# Secondary_Board_1_0.net
KiCad netlist of a schematic drawn in EAGLE
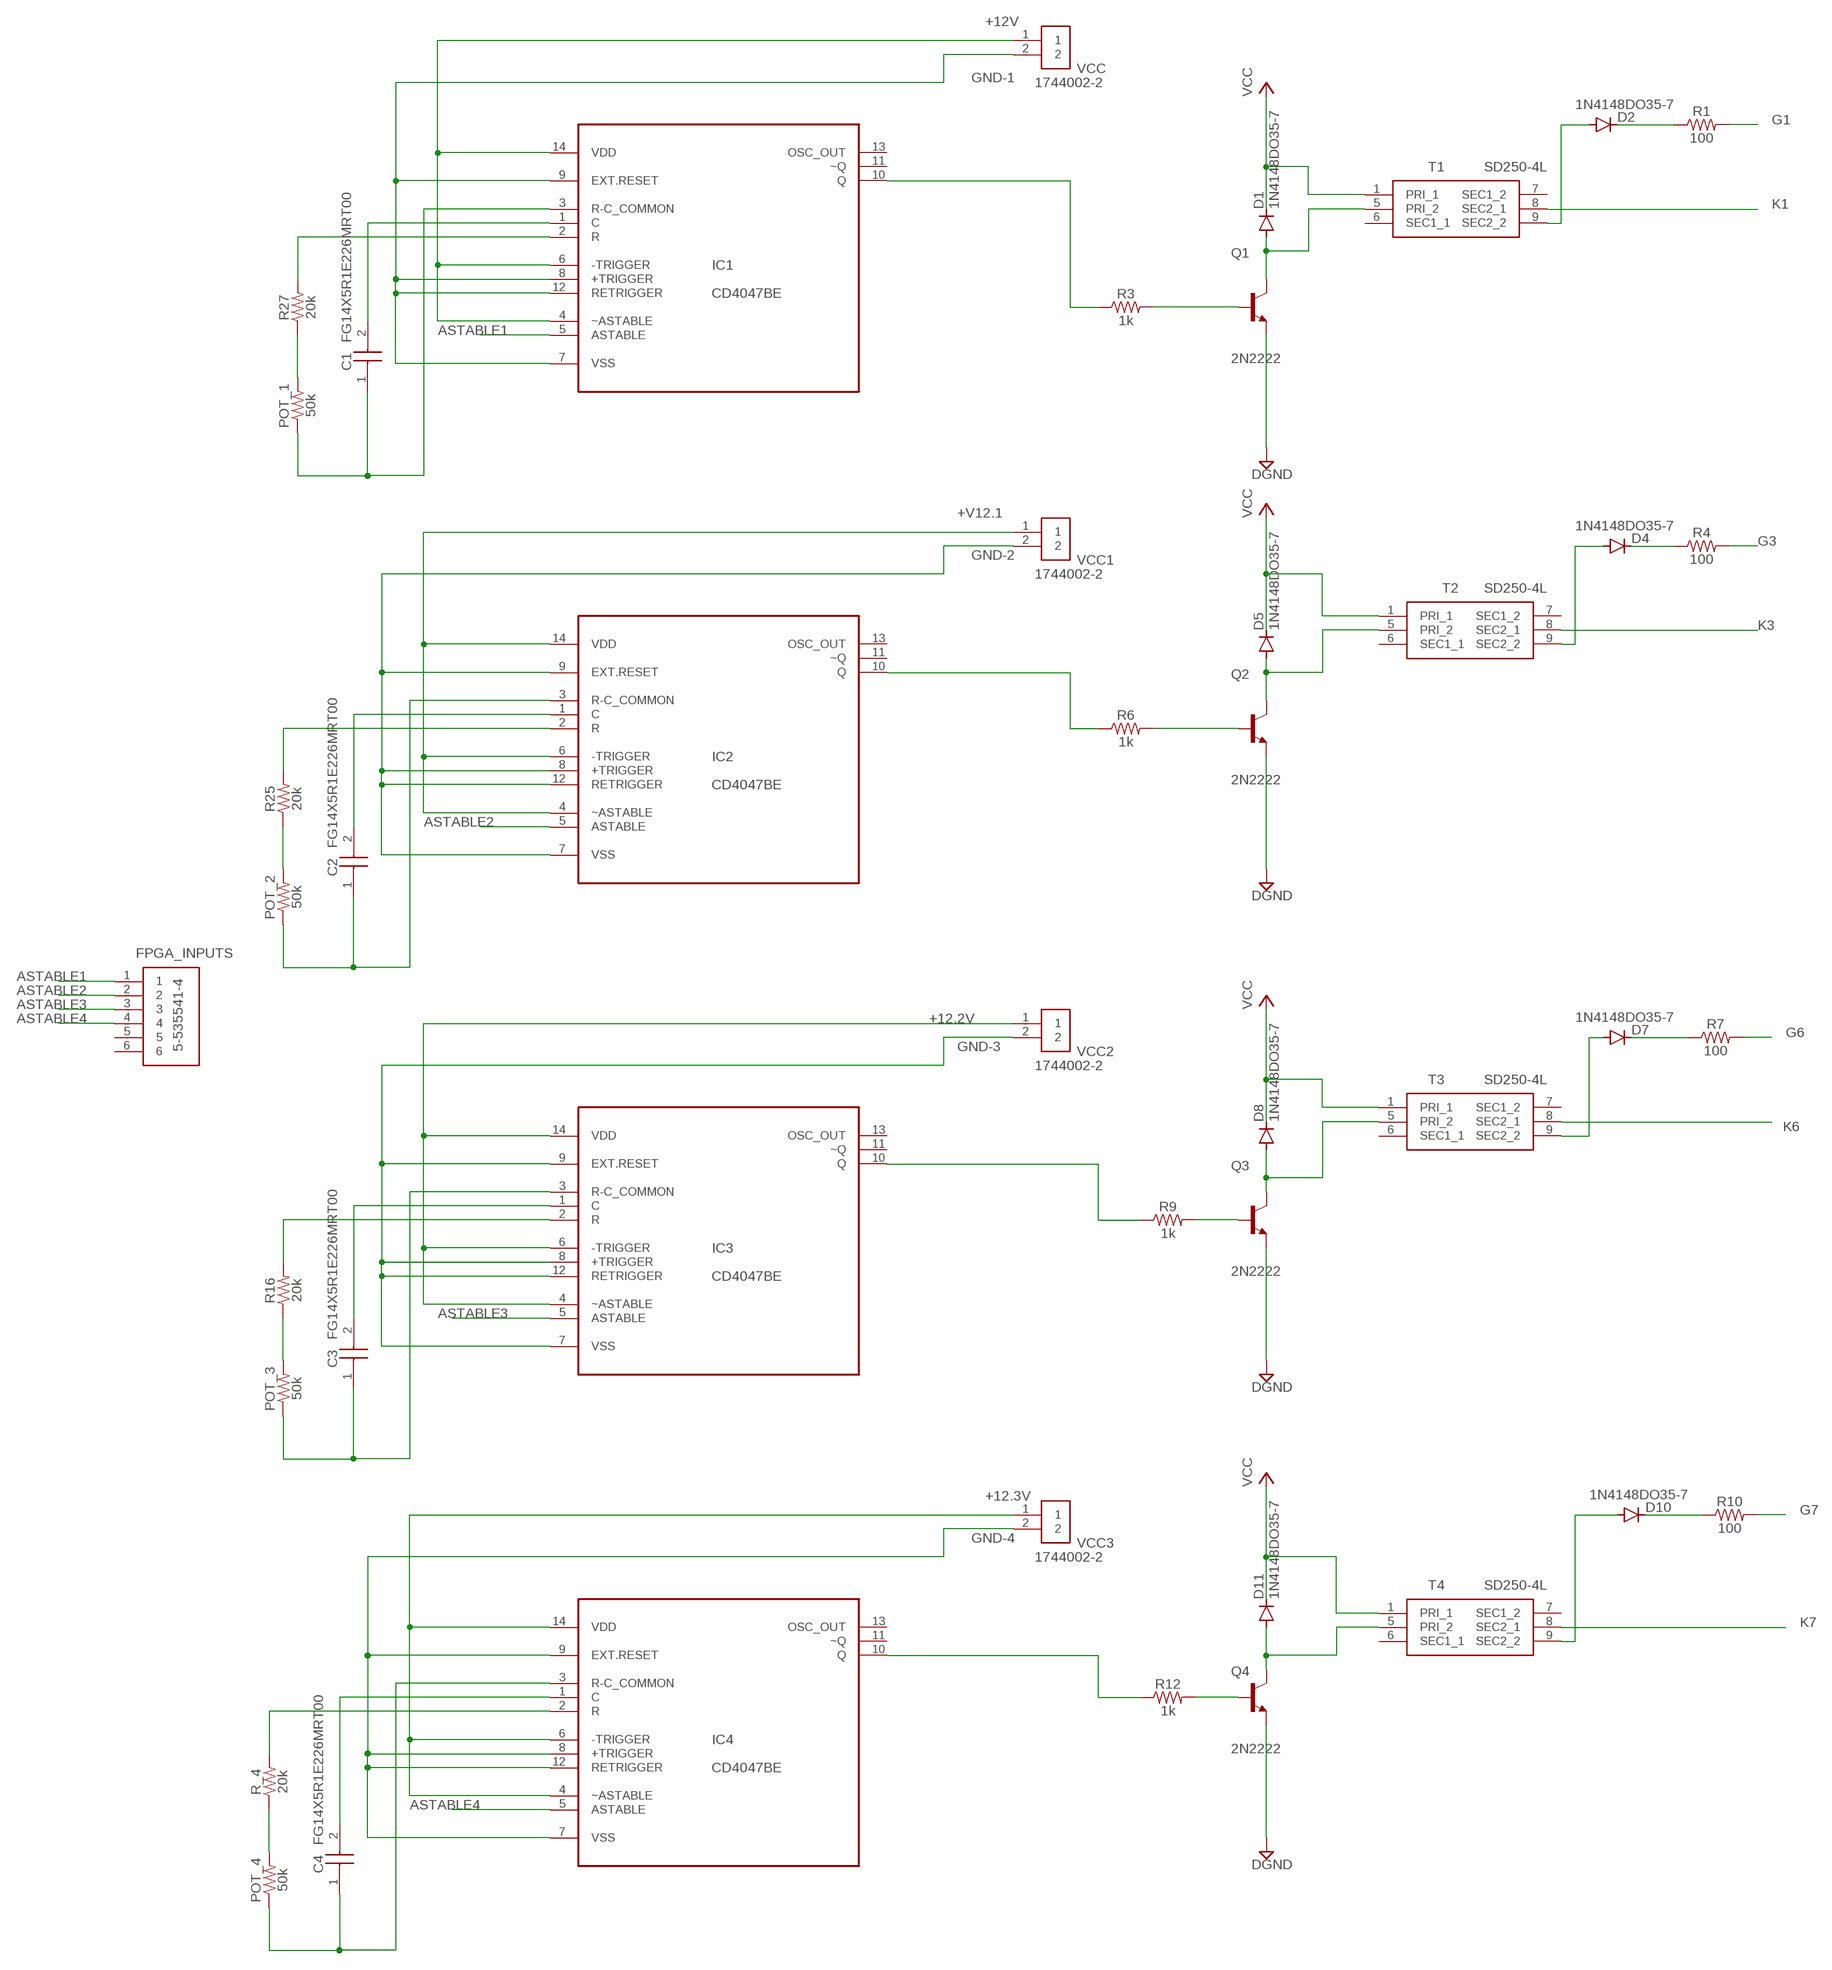
[diagram p0: schematic, sheet 1, part 1 of 2]
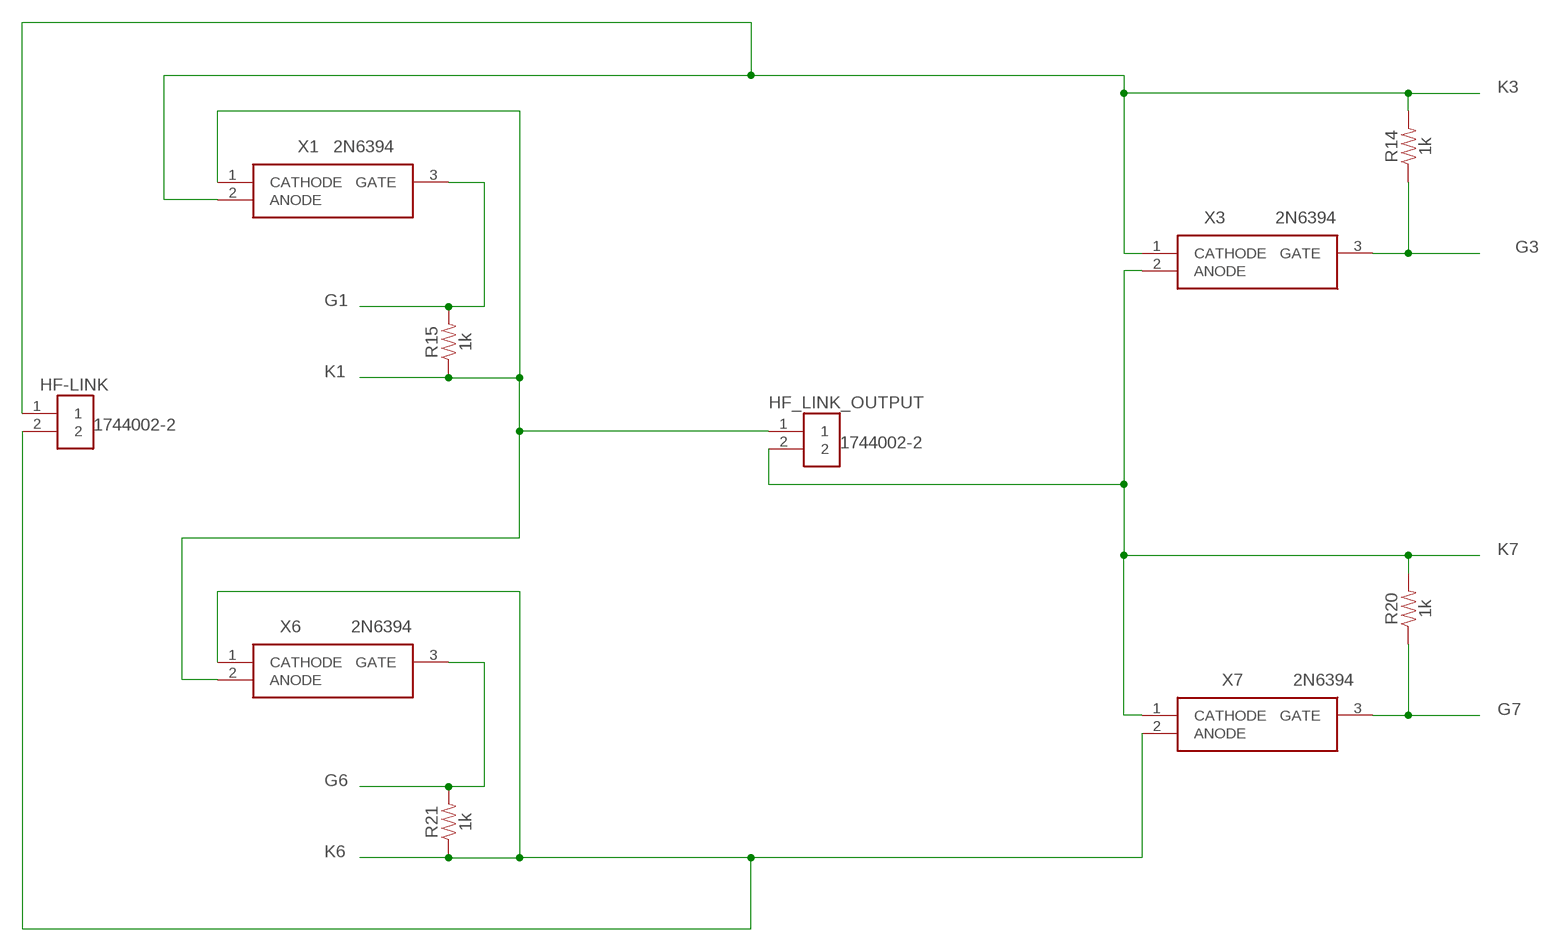
[diagram p1: schematic, sheet 1, part 2 of 2]

(export (version "E")
  (design (tool "Eeschema 10.0.6"))
  (components
    (comp (ref "C1")
      (value "FG14X5R1E226MRT00")
      (footprint "eagle-import:CAPPRD550W50D395H550")
      (libsource (lib "eagle-import") (part "FG14X5R1E226MRT00"))
    )
    (comp (ref "C2")
      (value "FG14X5R1E226MRT00")
      (footprint "eagle-import:CAPPRD550W50D395H550")
      (libsource (lib "eagle-import") (part "FG14X5R1E226MRT00"))
    )
    (comp (ref "C3")
      (value "FG14X5R1E226MRT00")
      (footprint "eagle-import:CAPPRD550W50D395H550")
      (libsource (lib "eagle-import") (part "FG14X5R1E226MRT00"))
    )
    (comp (ref "C4")
      (value "FG14X5R1E226MRT00")
      (footprint "eagle-import:CAPPRD550W50D395H550")
      (libsource (lib "eagle-import") (part "FG14X5R1E226MRT00"))
    )
    (comp (ref "D1")
      (value "1N4148DO35-7")
      (footprint "eagle-import:DO35-7")
      (libsource (lib "eagle-import") (part "1N4148DO35-7"))
    )
    (comp (ref "D2")
      (value "1N4148DO35-7")
      (footprint "eagle-import:DO35-7")
      (libsource (lib "eagle-import") (part "1N4148DO35-7"))
    )
    (comp (ref "D4")
      (value "1N4148DO35-7")
      (footprint "eagle-import:DO35-7")
      (libsource (lib "eagle-import") (part "1N4148DO35-7"))
    )
    (comp (ref "D5")
      (value "1N4148DO35-7")
      (footprint "eagle-import:DO35-7")
      (libsource (lib "eagle-import") (part "1N4148DO35-7"))
    )
    (comp (ref "D7")
      (value "1N4148DO35-7")
      (footprint "eagle-import:DO35-7")
      (libsource (lib "eagle-import") (part "1N4148DO35-7"))
    )
    (comp (ref "D8")
      (value "1N4148DO35-7")
      (footprint "eagle-import:DO35-7")
      (libsource (lib "eagle-import") (part "1N4148DO35-7"))
    )
    (comp (ref "D10")
      (value "1N4148DO35-7")
      (footprint "eagle-import:DO35-7")
      (libsource (lib "eagle-import") (part "1N4148DO35-7"))
    )
    (comp (ref "D11")
      (value "1N4148DO35-7")
      (footprint "eagle-import:DO35-7")
      (libsource (lib "eagle-import") (part "1N4148DO35-7"))
    )
    (comp (ref "FPGA_INPUTS")
      (value "5-535541-4")
      (footprint "eagle-import:SHDR6W76P0X254_1X6_1524X356X62")
      (fields (field (name "MOUSER_PART_NUMBER") "571-5-535541-4"))
      (libsource (lib "eagle-import") (part "5-535541-4"))
    )
    (comp (ref "HF-LINK")
      (value "1744002-2")
      (footprint "eagle-import:CONN_1744002-2")
      (fields (field (name "MF") "TE Connectivity"))
      (libsource (lib "eagle-import") (part "1744002-2"))
    )
    (comp (ref "HF_LINK_OUTPUT")
      (value "1744002-2")
      (footprint "eagle-import:CONN_1744002-2")
      (fields (field (name "MF") "TE Connectivity"))
      (libsource (lib "eagle-import") (part "1744002-2"))
    )
    (comp (ref "IC1")
      (value "CD4047BE")
      (footprint "eagle-import:DIP254P762X508-14")
      (fields (field (name "MF") "Texas Instruments"))
      (libsource (lib "eagle-import") (part "CD4047BE"))
    )
    (comp (ref "IC2")
      (value "CD4047BE")
      (footprint "eagle-import:DIP254P762X508-14")
      (fields (field (name "MF") "Texas Instruments"))
      (libsource (lib "eagle-import") (part "CD4047BE"))
    )
    (comp (ref "IC3")
      (value "CD4047BE")
      (footprint "eagle-import:DIP254P762X508-14")
      (fields (field (name "MF") "Texas Instruments"))
      (libsource (lib "eagle-import") (part "CD4047BE"))
    )
    (comp (ref "IC4")
      (value "CD4047BE")
      (footprint "eagle-import:DIP254P762X508-14")
      (fields (field (name "MF") "Texas Instruments"))
      (libsource (lib "eagle-import") (part "CD4047BE"))
    )
    (comp (ref "POT_1")
      (value "50k")
      (footprint "eagle-import:AXIAL-0.3")
      (libsource (lib "eagle-import") (part "1KOHM-HORIZ-1/4W-1%"))
    )
    (comp (ref "POT_2")
      (value "50k")
      (footprint "eagle-import:AXIAL-0.3")
      (libsource (lib "eagle-import") (part "1KOHM-HORIZ-1/4W-1%"))
    )
    (comp (ref "POT_3")
      (value "50k")
      (footprint "eagle-import:AXIAL-0.3")
      (libsource (lib "eagle-import") (part "1KOHM-HORIZ-1/4W-1%"))
    )
    (comp (ref "POT_4")
      (value "50k")
      (footprint "eagle-import:AXIAL-0.3")
      (libsource (lib "eagle-import") (part "1KOHM-HORIZ-1/4W-1%"))
    )
    (comp (ref "Q1")
      (value "2N2222")
      (footprint "eagle-import:TO127P584H533-3")
      (fields (field (name "MF") "Central Semiconductor"))
      (libsource (lib "eagle-import") (part "2N2222"))
    )
    (comp (ref "Q2")
      (value "2N2222")
      (footprint "eagle-import:TO127P584H533-3")
      (fields (field (name "MF") "Central Semiconductor"))
      (libsource (lib "eagle-import") (part "2N2222"))
    )
    (comp (ref "Q3")
      (value "2N2222")
      (footprint "eagle-import:TO127P584H533-3")
      (fields (field (name "MF") "Central Semiconductor"))
      (libsource (lib "eagle-import") (part "2N2222"))
    )
    (comp (ref "Q4")
      (value "2N2222")
      (footprint "eagle-import:TO127P584H533-3")
      (fields (field (name "MF") "Central Semiconductor"))
      (libsource (lib "eagle-import") (part "2N2222"))
    )
    (comp (ref "R1")
      (value "100")
      (footprint "eagle-import:AXIAL-0.3")
      (libsource (lib "eagle-import") (part "100OHM-HORIZ-1/4W-1%"))
    )
    (comp (ref "R3")
      (value "1k")
      (footprint "eagle-import:AXIAL-0.3")
      (libsource (lib "eagle-import") (part "1KOHM-HORIZ-1/4W-1%"))
    )
    (comp (ref "R4")
      (value "100")
      (footprint "eagle-import:AXIAL-0.3")
      (libsource (lib "eagle-import") (part "100OHM-HORIZ-1/4W-1%"))
    )
    (comp (ref "R6")
      (value "1k")
      (footprint "eagle-import:AXIAL-0.3")
      (libsource (lib "eagle-import") (part "1KOHM-HORIZ-1/4W-1%"))
    )
    (comp (ref "R7")
      (value "100")
      (footprint "eagle-import:AXIAL-0.3")
      (libsource (lib "eagle-import") (part "100OHM-HORIZ-1/4W-1%"))
    )
    (comp (ref "R9")
      (value "1k")
      (footprint "eagle-import:AXIAL-0.3")
      (libsource (lib "eagle-import") (part "1KOHM-HORIZ-1/4W-1%"))
    )
    (comp (ref "R10")
      (value "100")
      (footprint "eagle-import:AXIAL-0.3")
      (libsource (lib "eagle-import") (part "100OHM-HORIZ-1/4W-1%"))
    )
    (comp (ref "R12")
      (value "1k")
      (footprint "eagle-import:AXIAL-0.3")
      (libsource (lib "eagle-import") (part "1KOHM-HORIZ-1/4W-1%"))
    )
    (comp (ref "R14")
      (value "1k")
      (footprint "eagle-import:AXIAL-0.3")
      (libsource (lib "eagle-import") (part "1KOHM-HORIZ-1/4W-1%"))
    )
    (comp (ref "R15")
      (value "1k")
      (footprint "eagle-import:AXIAL-0.3")
      (libsource (lib "eagle-import") (part "1KOHM-HORIZ-1/4W-1%"))
    )
    (comp (ref "R16")
      (value "20k")
      (footprint "eagle-import:AXIAL-0.3")
      (libsource (lib "eagle-import") (part "1KOHM-HORIZ-1/4W-1%"))
    )
    (comp (ref "R20")
      (value "1k")
      (footprint "eagle-import:AXIAL-0.3")
      (libsource (lib "eagle-import") (part "1KOHM-HORIZ-1/4W-1%"))
    )
    (comp (ref "R21")
      (value "1k")
      (footprint "eagle-import:AXIAL-0.3")
      (libsource (lib "eagle-import") (part "1KOHM-HORIZ-1/4W-1%"))
    )
    (comp (ref "R25")
      (value "20k")
      (footprint "eagle-import:AXIAL-0.3")
      (libsource (lib "eagle-import") (part "1KOHM-HORIZ-1/4W-1%"))
    )
    (comp (ref "R27")
      (value "20k")
      (footprint "eagle-import:AXIAL-0.3")
      (libsource (lib "eagle-import") (part "1KOHM-HORIZ-1/4W-1%"))
    )
    (comp (ref "R_4")
      (value "20k")
      (footprint "eagle-import:AXIAL-0.3")
      (libsource (lib "eagle-import") (part "1KOHM-HORIZ-1/4W-1%"))
    )
    (comp (ref "T1")
      (value "SD250-4L")
      (footprint "eagle-import:SD2504L")
      (libsource (lib "eagle-import") (part "SD250-4L"))
    )
    (comp (ref "T2")
      (value "SD250-4L")
      (footprint "eagle-import:SD2504L")
      (libsource (lib "eagle-import") (part "SD250-4L"))
    )
    (comp (ref "T3")
      (value "SD250-4L")
      (footprint "eagle-import:SD2504L")
      (libsource (lib "eagle-import") (part "SD250-4L"))
    )
    (comp (ref "T4")
      (value "SD250-4L")
      (footprint "eagle-import:SD2504L")
      (libsource (lib "eagle-import") (part "SD250-4L"))
    )
    (comp (ref "VCC")
      (value "1744002-2")
      (footprint "eagle-import:CONN_1744002-2")
      (fields (field (name "MF") "TE Connectivity"))
      (libsource (lib "eagle-import") (part "1744002-2"))
    )
    (comp (ref "VCC1")
      (value "1744002-2")
      (footprint "eagle-import:CONN_1744002-2")
      (fields (field (name "MF") "TE Connectivity"))
      (libsource (lib "eagle-import") (part "1744002-2"))
    )
    (comp (ref "VCC2")
      (value "1744002-2")
      (footprint "eagle-import:CONN_1744002-2")
      (fields (field (name "MF") "TE Connectivity"))
      (libsource (lib "eagle-import") (part "1744002-2"))
    )
    (comp (ref "VCC3")
      (value "1744002-2")
      (footprint "eagle-import:CONN_1744002-2")
      (fields (field (name "MF") "TE Connectivity"))
      (libsource (lib "eagle-import") (part "1744002-2"))
    )
    (comp (ref "X1")
      (value "2N6394")
      (footprint "eagle-import:TO254P482X997X2018-3P")
      (fields (field (name "MOUSER_PART_NUMBER") "863-2N6394"))
      (libsource (lib "eagle-import") (part "2N6394"))
    )
    (comp (ref "X3")
      (value "2N6394")
      (footprint "eagle-import:TO254P482X997X2018-3P")
      (fields (field (name "MOUSER_PART_NUMBER") "863-2N6394"))
      (libsource (lib "eagle-import") (part "2N6394"))
    )
    (comp (ref "X6")
      (value "2N6394")
      (footprint "eagle-import:TO254P482X997X2018-3P")
      (fields (field (name "MOUSER_PART_NUMBER") "863-2N6394"))
      (libsource (lib "eagle-import") (part "2N6394"))
    )
    (comp (ref "X7")
      (value "2N6394")
      (footprint "eagle-import:TO254P482X997X2018-3P")
      (fields (field (name "MOUSER_PART_NUMBER") "863-2N6394"))
      (libsource (lib "eagle-import") (part "2N6394"))
    )
  )
  (nets
    (net (code "1") (name "/+12.2V") (class "Default")
      (node (ref "IC3") (pin "14") (pinfunction "VDD_14") (pintype "power_in"))
      (node (ref "IC3") (pin "4") (pinfunction "~{ASTABLE}_4") (pintype "input"))
      (node (ref "IC3") (pin "6") (pinfunction "-TRIGGER_6") (pintype "power_in"))
      (node (ref "VCC2") (pin "1") (pinfunction "1_1") (pintype "passive"))
    )
    (net (code "2") (name "/+12.3V") (class "Default")
      (node (ref "IC4") (pin "14") (pinfunction "VDD_14") (pintype "power_in"))
      (node (ref "IC4") (pin "4") (pinfunction "~{ASTABLE}_4") (pintype "input"))
      (node (ref "IC4") (pin "6") (pinfunction "-TRIGGER_6") (pintype "power_in"))
      (node (ref "VCC3") (pin "1") (pinfunction "1_1") (pintype "passive"))
    )
    (net (code "3") (name "/+12V") (class "Default")
      (node (ref "IC1") (pin "14") (pinfunction "VDD_14") (pintype "power_in"))
      (node (ref "IC1") (pin "4") (pinfunction "~{ASTABLE}_4") (pintype "input"))
      (node (ref "IC1") (pin "6") (pinfunction "-TRIGGER_6") (pintype "power_in"))
      (node (ref "VCC") (pin "1") (pinfunction "1_1") (pintype "passive"))
    )
    (net (code "4") (name "/+V12.1") (class "Default")
      (node (ref "IC2") (pin "14") (pinfunction "VDD_14") (pintype "power_in"))
      (node (ref "IC2") (pin "4") (pinfunction "~{ASTABLE}_4") (pintype "input"))
      (node (ref "IC2") (pin "6") (pinfunction "-TRIGGER_6") (pintype "power_in"))
      (node (ref "VCC1") (pin "1") (pinfunction "1_1") (pintype "passive"))
    )
    (net (code "5") (name "/ASTABLE1") (class "Default")
      (node (ref "FPGA_INPUTS") (pin "1") (pinfunction "1_1") (pintype "bidirectional"))
      (node (ref "IC1") (pin "5") (pinfunction "ASTABLE_5") (pintype "input"))
    )
    (net (code "6") (name "/ASTABLE2") (class "Default")
      (node (ref "FPGA_INPUTS") (pin "2") (pinfunction "2_2") (pintype "bidirectional"))
      (node (ref "IC2") (pin "5") (pinfunction "ASTABLE_5") (pintype "input"))
    )
    (net (code "7") (name "/ASTABLE3") (class "Default")
      (node (ref "FPGA_INPUTS") (pin "3") (pinfunction "3_3") (pintype "bidirectional"))
      (node (ref "IC3") (pin "5") (pinfunction "ASTABLE_5") (pintype "input"))
    )
    (net (code "8") (name "/ASTABLE4") (class "Default")
      (node (ref "FPGA_INPUTS") (pin "4") (pinfunction "4_4") (pintype "bidirectional"))
      (node (ref "IC4") (pin "5") (pinfunction "ASTABLE_5") (pintype "input"))
    )
    (net (code "9") (name "/G1") (class "Default")
      (node (ref "R1") (pin "P$2") (pinfunction "2_P$2") (pintype "passive"))
      (node (ref "R15") (pin "P$2") (pinfunction "2_P$2") (pintype "passive"))
      (node (ref "X1") (pin "3") (pinfunction "GATE_3") (pintype "bidirectional"))
    )
    (net (code "10") (name "/G3") (class "Default")
      (node (ref "R14") (pin "P$1") (pinfunction "1_P$1") (pintype "passive"))
      (node (ref "R4") (pin "P$2") (pinfunction "2_P$2") (pintype "passive"))
      (node (ref "X3") (pin "3") (pinfunction "GATE_3") (pintype "bidirectional"))
    )
    (net (code "11") (name "/G6") (class "Default")
      (node (ref "R21") (pin "P$2") (pinfunction "2_P$2") (pintype "passive"))
      (node (ref "R7") (pin "P$2") (pinfunction "2_P$2") (pintype "passive"))
      (node (ref "X6") (pin "3") (pinfunction "GATE_3") (pintype "bidirectional"))
    )
    (net (code "12") (name "/G7") (class "Default")
      (node (ref "R10") (pin "P$2") (pinfunction "2_P$2") (pintype "passive"))
      (node (ref "R20") (pin "P$1") (pinfunction "1_P$1") (pintype "passive"))
      (node (ref "X7") (pin "3") (pinfunction "GATE_3") (pintype "bidirectional"))
    )
    (net (code "13") (name "/GND-1") (class "Default")
      (node (ref "IC1") (pin "12") (pinfunction "RETRIGGER_12") (pintype "input"))
      (node (ref "IC1") (pin "7") (pinfunction "VSS_7") (pintype "power_in"))
      (node (ref "IC1") (pin "8") (pinfunction "+TRIGGER_8") (pintype "input"))
      (node (ref "IC1") (pin "9") (pinfunction "EXT.RESET_9") (pintype "input"))
      (node (ref "VCC") (pin "2") (pinfunction "2_2") (pintype "passive"))
    )
    (net (code "14") (name "/GND-2") (class "Default")
      (node (ref "IC2") (pin "12") (pinfunction "RETRIGGER_12") (pintype "input"))
      (node (ref "IC2") (pin "7") (pinfunction "VSS_7") (pintype "power_in"))
      (node (ref "IC2") (pin "8") (pinfunction "+TRIGGER_8") (pintype "input"))
      (node (ref "IC2") (pin "9") (pinfunction "EXT.RESET_9") (pintype "input"))
      (node (ref "VCC1") (pin "2") (pinfunction "2_2") (pintype "passive"))
    )
    (net (code "15") (name "/GND-3") (class "Default")
      (node (ref "IC3") (pin "12") (pinfunction "RETRIGGER_12") (pintype "input"))
      (node (ref "IC3") (pin "7") (pinfunction "VSS_7") (pintype "power_in"))
      (node (ref "IC3") (pin "8") (pinfunction "+TRIGGER_8") (pintype "input"))
      (node (ref "IC3") (pin "9") (pinfunction "EXT.RESET_9") (pintype "input"))
      (node (ref "VCC2") (pin "2") (pinfunction "2_2") (pintype "passive"))
    )
    (net (code "16") (name "/GND-4") (class "Default")
      (node (ref "IC4") (pin "12") (pinfunction "RETRIGGER_12") (pintype "input"))
      (node (ref "IC4") (pin "7") (pinfunction "VSS_7") (pintype "power_in"))
      (node (ref "IC4") (pin "8") (pinfunction "+TRIGGER_8") (pintype "input"))
      (node (ref "IC4") (pin "9") (pinfunction "EXT.RESET_9") (pintype "input"))
      (node (ref "VCC3") (pin "2") (pinfunction "2_2") (pintype "passive"))
    )
    (net (code "17") (name "/K1") (class "Default")
      (node (ref "HF_LINK_OUTPUT") (pin "1") (pinfunction "1_1") (pintype "passive"))
      (node (ref "R15") (pin "P$1") (pinfunction "1_P$1") (pintype "passive"))
      (node (ref "T1") (pin "8") (pinfunction "SEC2_1_8") (pintype "bidirectional"))
      (node (ref "X1") (pin "1") (pinfunction "CATHODE_1") (pintype "bidirectional"))
      (node (ref "X6") (pin "2") (pinfunction "ANODE_2") (pintype "bidirectional"))
    )
    (net (code "18") (name "/K3") (class "Default")
      (node (ref "HF-LINK") (pin "1") (pinfunction "1_1") (pintype "passive"))
      (node (ref "R14") (pin "P$2") (pinfunction "2_P$2") (pintype "passive"))
      (node (ref "T2") (pin "8") (pinfunction "SEC2_1_8") (pintype "bidirectional"))
      (node (ref "X1") (pin "2") (pinfunction "ANODE_2") (pintype "bidirectional"))
      (node (ref "X3") (pin "1") (pinfunction "CATHODE_1") (pintype "bidirectional"))
    )
    (net (code "19") (name "/K6") (class "Default")
      (node (ref "HF-LINK") (pin "2") (pinfunction "2_2") (pintype "passive"))
      (node (ref "R21") (pin "P$1") (pinfunction "1_P$1") (pintype "passive"))
      (node (ref "T3") (pin "8") (pinfunction "SEC2_1_8") (pintype "bidirectional"))
      (node (ref "X6") (pin "1") (pinfunction "CATHODE_1") (pintype "bidirectional"))
      (node (ref "X7") (pin "2") (pinfunction "ANODE_2") (pintype "bidirectional"))
    )
    (net (code "20") (name "/K7") (class "Default")
      (node (ref "HF_LINK_OUTPUT") (pin "2") (pinfunction "2_2") (pintype "passive"))
      (node (ref "R20") (pin "P$2") (pinfunction "2_P$2") (pintype "passive"))
      (node (ref "T4") (pin "8") (pinfunction "SEC2_1_8") (pintype "bidirectional"))
      (node (ref "X3") (pin "2") (pinfunction "ANODE_2") (pintype "bidirectional"))
      (node (ref "X7") (pin "1") (pinfunction "CATHODE_1") (pintype "bidirectional"))
    )
    (net (code "21") (name "DGND") (class "Default")
      (node (ref "Q1") (pin "1") (pinfunction "E_1") (pintype "passive"))
      (node (ref "Q2") (pin "1") (pinfunction "E_1") (pintype "passive"))
      (node (ref "Q3") (pin "1") (pinfunction "E_1") (pintype "passive"))
      (node (ref "Q4") (pin "1") (pinfunction "E_1") (pintype "passive"))
    )
    (net (code "22") (name "Net-(C1-+)") (class "Default")
      (node (ref "C1") (pin "1") (pinfunction "+_1") (pintype "bidirectional"))
      (node (ref "IC1") (pin "3") (pinfunction "R-C_COMMON_3") (pintype "input"))
      (node (ref "POT_1") (pin "P$1") (pinfunction "1_P$1") (pintype "passive"))
    )
    (net (code "23") (name "Net-(C1--)") (class "Default")
      (node (ref "C1") (pin "2") (pinfunction "-_2") (pintype "bidirectional"))
      (node (ref "IC1") (pin "1") (pinfunction "C_1") (pintype "input"))
    )
    (net (code "24") (name "Net-(C2-+)") (class "Default")
      (node (ref "C2") (pin "1") (pinfunction "+_1") (pintype "bidirectional"))
      (node (ref "IC2") (pin "3") (pinfunction "R-C_COMMON_3") (pintype "input"))
      (node (ref "POT_2") (pin "P$1") (pinfunction "1_P$1") (pintype "passive"))
    )
    (net (code "25") (name "Net-(C2--)") (class "Default")
      (node (ref "C2") (pin "2") (pinfunction "-_2") (pintype "bidirectional"))
      (node (ref "IC2") (pin "1") (pinfunction "C_1") (pintype "input"))
    )
    (net (code "26") (name "Net-(C3-+)") (class "Default")
      (node (ref "C3") (pin "1") (pinfunction "+_1") (pintype "bidirectional"))
      (node (ref "IC3") (pin "3") (pinfunction "R-C_COMMON_3") (pintype "input"))
      (node (ref "POT_3") (pin "P$1") (pinfunction "1_P$1") (pintype "passive"))
    )
    (net (code "27") (name "Net-(C3--)") (class "Default")
      (node (ref "C3") (pin "2") (pinfunction "-_2") (pintype "bidirectional"))
      (node (ref "IC3") (pin "1") (pinfunction "C_1") (pintype "input"))
    )
    (net (code "28") (name "Net-(C4-+)") (class "Default")
      (node (ref "C4") (pin "1") (pinfunction "+_1") (pintype "bidirectional"))
      (node (ref "IC4") (pin "3") (pinfunction "R-C_COMMON_3") (pintype "input"))
      (node (ref "POT_4") (pin "P$1") (pinfunction "1_P$1") (pintype "passive"))
    )
    (net (code "29") (name "Net-(C4--)") (class "Default")
      (node (ref "C4") (pin "2") (pinfunction "-_2") (pintype "bidirectional"))
      (node (ref "IC4") (pin "1") (pinfunction "C_1") (pintype "input"))
    )
    (net (code "30") (name "Net-(IC1-Q)") (class "Default")
      (node (ref "IC1") (pin "10") (pinfunction "Q_10") (pintype "output"))
      (node (ref "R3") (pin "P$1") (pinfunction "1_P$1") (pintype "passive"))
    )
    (net (code "31") (name "Net-(IC1-R)") (class "Default")
      (node (ref "IC1") (pin "2") (pinfunction "R_2") (pintype "input"))
      (node (ref "R27") (pin "P$2") (pinfunction "2_P$2") (pintype "passive"))
    )
    (net (code "32") (name "Net-(IC2-Q)") (class "Default")
      (node (ref "IC2") (pin "10") (pinfunction "Q_10") (pintype "output"))
      (node (ref "R6") (pin "P$1") (pinfunction "1_P$1") (pintype "passive"))
    )
    (net (code "33") (name "Net-(IC2-R)") (class "Default")
      (node (ref "IC2") (pin "2") (pinfunction "R_2") (pintype "input"))
      (node (ref "R25") (pin "P$2") (pinfunction "2_P$2") (pintype "passive"))
    )
    (net (code "34") (name "Net-(IC3-Q)") (class "Default")
      (node (ref "IC3") (pin "10") (pinfunction "Q_10") (pintype "output"))
      (node (ref "R9") (pin "P$1") (pinfunction "1_P$1") (pintype "passive"))
    )
    (net (code "35") (name "Net-(IC3-R)") (class "Default")
      (node (ref "IC3") (pin "2") (pinfunction "R_2") (pintype "input"))
      (node (ref "R16") (pin "P$2") (pinfunction "2_P$2") (pintype "passive"))
    )
    (net (code "36") (name "Net-(IC4-Q)") (class "Default")
      (node (ref "IC4") (pin "10") (pinfunction "Q_10") (pintype "output"))
      (node (ref "R12") (pin "P$1") (pinfunction "1_P$1") (pintype "passive"))
    )
    (net (code "37") (name "Net-(IC4-R)") (class "Default")
      (node (ref "IC4") (pin "2") (pinfunction "R_2") (pintype "input"))
      (node (ref "R_4") (pin "P$2") (pinfunction "2_P$2") (pintype "passive"))
    )
    (net (code "38") (name "Net-(POT_1-2)") (class "Default")
      (node (ref "POT_1") (pin "P$2") (pinfunction "2_P$2") (pintype "passive"))
      (node (ref "R27") (pin "P$1") (pinfunction "1_P$1") (pintype "passive"))
    )
    (net (code "39") (name "Net-(POT_2-2)") (class "Default")
      (node (ref "POT_2") (pin "P$2") (pinfunction "2_P$2") (pintype "passive"))
      (node (ref "R25") (pin "P$1") (pinfunction "1_P$1") (pintype "passive"))
    )
    (net (code "40") (name "Net-(POT_3-2)") (class "Default")
      (node (ref "POT_3") (pin "P$2") (pinfunction "2_P$2") (pintype "passive"))
      (node (ref "R16") (pin "P$1") (pinfunction "1_P$1") (pintype "passive"))
    )
    (net (code "41") (name "Net-(POT_4-2)") (class "Default")
      (node (ref "POT_4") (pin "P$2") (pinfunction "2_P$2") (pintype "passive"))
      (node (ref "R_4") (pin "P$1") (pinfunction "1_P$1") (pintype "passive"))
    )
    (net (code "42") (name "Net-(Q1-B)") (class "Default")
      (node (ref "Q1") (pin "2") (pinfunction "B_2") (pintype "passive"))
      (node (ref "R3") (pin "P$2") (pinfunction "2_P$2") (pintype "passive"))
    )
    (net (code "43") (name "Net-(Q1-C)") (class "Default")
      (node (ref "D1") (pin "A") (pinfunction "A_A") (pintype "passive"))
      (node (ref "Q1") (pin "3") (pinfunction "C_3") (pintype "passive"))
      (node (ref "T1") (pin "5") (pinfunction "PRI_2_5") (pintype "bidirectional"))
    )
    (net (code "44") (name "Net-(Q2-B)") (class "Default")
      (node (ref "Q2") (pin "2") (pinfunction "B_2") (pintype "passive"))
      (node (ref "R6") (pin "P$2") (pinfunction "2_P$2") (pintype "passive"))
    )
    (net (code "45") (name "Net-(Q2-C)") (class "Default")
      (node (ref "D5") (pin "A") (pinfunction "A_A") (pintype "passive"))
      (node (ref "Q2") (pin "3") (pinfunction "C_3") (pintype "passive"))
      (node (ref "T2") (pin "5") (pinfunction "PRI_2_5") (pintype "bidirectional"))
    )
    (net (code "46") (name "Net-(Q3-B)") (class "Default")
      (node (ref "Q3") (pin "2") (pinfunction "B_2") (pintype "passive"))
      (node (ref "R9") (pin "P$2") (pinfunction "2_P$2") (pintype "passive"))
    )
    (net (code "47") (name "Net-(Q3-C)") (class "Default")
      (node (ref "D8") (pin "A") (pinfunction "A_A") (pintype "passive"))
      (node (ref "Q3") (pin "3") (pinfunction "C_3") (pintype "passive"))
      (node (ref "T3") (pin "5") (pinfunction "PRI_2_5") (pintype "bidirectional"))
    )
    (net (code "48") (name "Net-(Q4-B)") (class "Default")
      (node (ref "Q4") (pin "2") (pinfunction "B_2") (pintype "passive"))
      (node (ref "R12") (pin "P$2") (pinfunction "2_P$2") (pintype "passive"))
    )
    (net (code "49") (name "Net-(Q4-C)") (class "Default")
      (node (ref "D11") (pin "A") (pinfunction "A_A") (pintype "passive"))
      (node (ref "Q4") (pin "3") (pinfunction "C_3") (pintype "passive"))
      (node (ref "T4") (pin "5") (pinfunction "PRI_2_5") (pintype "bidirectional"))
    )
    (net (code "50") (name "Net-(R1-1)") (class "Default")
      (node (ref "D2") (pin "C") (pinfunction "C_C") (pintype "passive"))
      (node (ref "R1") (pin "P$1") (pinfunction "1_P$1") (pintype "passive"))
    )
    (net (code "51") (name "Net-(R4-1)") (class "Default")
      (node (ref "D4") (pin "C") (pinfunction "C_C") (pintype "passive"))
      (node (ref "R4") (pin "P$1") (pinfunction "1_P$1") (pintype "passive"))
    )
    (net (code "52") (name "Net-(R7-1)") (class "Default")
      (node (ref "D7") (pin "C") (pinfunction "C_C") (pintype "passive"))
      (node (ref "R7") (pin "P$1") (pinfunction "1_P$1") (pintype "passive"))
    )
    (net (code "53") (name "Net-(R10-1)") (class "Default")
      (node (ref "D10") (pin "C") (pinfunction "C_C") (pintype "passive"))
      (node (ref "R10") (pin "P$1") (pinfunction "1_P$1") (pintype "passive"))
    )
    (net (code "54") (name "Net-(T1-SEC2_2)") (class "Default")
      (node (ref "D2") (pin "A") (pinfunction "A_A") (pintype "passive"))
      (node (ref "T1") (pin "9") (pinfunction "SEC2_2_9") (pintype "bidirectional"))
    )
    (net (code "55") (name "Net-(T2-SEC2_2)") (class "Default")
      (node (ref "D4") (pin "A") (pinfunction "A_A") (pintype "passive"))
      (node (ref "T2") (pin "9") (pinfunction "SEC2_2_9") (pintype "bidirectional"))
    )
    (net (code "56") (name "Net-(T3-SEC2_2)") (class "Default")
      (node (ref "D7") (pin "A") (pinfunction "A_A") (pintype "passive"))
      (node (ref "T3") (pin "9") (pinfunction "SEC2_2_9") (pintype "bidirectional"))
    )
    (net (code "57") (name "Net-(T4-SEC2_2)") (class "Default")
      (node (ref "D10") (pin "A") (pinfunction "A_A") (pintype "passive"))
      (node (ref "T4") (pin "9") (pinfunction "SEC2_2_9") (pintype "bidirectional"))
    )
    (net (code "58") (name "VCC") (class "Default")
      (node (ref "D1") (pin "C") (pinfunction "C_C") (pintype "passive"))
      (node (ref "D11") (pin "C") (pinfunction "C_C") (pintype "passive"))
      (node (ref "D5") (pin "C") (pinfunction "C_C") (pintype "passive"))
      (node (ref "D8") (pin "C") (pinfunction "C_C") (pintype "passive"))
      (node (ref "T1") (pin "1") (pinfunction "PRI_1_1") (pintype "bidirectional"))
      (node (ref "T2") (pin "1") (pinfunction "PRI_1_1") (pintype "bidirectional"))
      (node (ref "T3") (pin "1") (pinfunction "PRI_1_1") (pintype "bidirectional"))
      (node (ref "T4") (pin "1") (pinfunction "PRI_1_1") (pintype "bidirectional"))
    )
    (net (code "59") (name "unconnected-(FPGA_INPUTS-Pad5)") (class "Default")
      (node (ref "FPGA_INPUTS") (pin "5") (pinfunction "5_5") (pintype "bidirectional"))
    )
    (net (code "60") (name "unconnected-(FPGA_INPUTS-Pad6)") (class "Default")
      (node (ref "FPGA_INPUTS") (pin "6") (pinfunction "6_6") (pintype "bidirectional"))
    )
    (net (code "61") (name "unconnected-(IC1-OSC_OUT-Pad13)") (class "Default")
      (node (ref "IC1") (pin "13") (pinfunction "OSC_OUT_13") (pintype "output"))
    )
    (net (code "62") (name "unconnected-(IC1-~{Q}-Pad11)") (class "Default")
      (node (ref "IC1") (pin "11") (pinfunction "~{Q}_11") (pintype "output"))
    )
    (net (code "63") (name "unconnected-(IC2-OSC_OUT-Pad13)") (class "Default")
      (node (ref "IC2") (pin "13") (pinfunction "OSC_OUT_13") (pintype "output"))
    )
    (net (code "64") (name "unconnected-(IC2-~{Q}-Pad11)") (class "Default")
      (node (ref "IC2") (pin "11") (pinfunction "~{Q}_11") (pintype "output"))
    )
    (net (code "65") (name "unconnected-(IC3-OSC_OUT-Pad13)") (class "Default")
      (node (ref "IC3") (pin "13") (pinfunction "OSC_OUT_13") (pintype "output"))
    )
    (net (code "66") (name "unconnected-(IC3-~{Q}-Pad11)") (class "Default")
      (node (ref "IC3") (pin "11") (pinfunction "~{Q}_11") (pintype "output"))
    )
    (net (code "67") (name "unconnected-(IC4-OSC_OUT-Pad13)") (class "Default")
      (node (ref "IC4") (pin "13") (pinfunction "OSC_OUT_13") (pintype "output"))
    )
    (net (code "68") (name "unconnected-(IC4-~{Q}-Pad11)") (class "Default")
      (node (ref "IC4") (pin "11") (pinfunction "~{Q}_11") (pintype "output"))
    )
    (net (code "69") (name "unconnected-(T1-SEC1_1-Pad6)") (class "Default")
      (node (ref "T1") (pin "6") (pinfunction "SEC1_1_6") (pintype "bidirectional"))
    )
    (net (code "70") (name "unconnected-(T1-SEC1_2-Pad7)") (class "Default")
      (node (ref "T1") (pin "7") (pinfunction "SEC1_2_7") (pintype "bidirectional"))
    )
    (net (code "71") (name "unconnected-(T2-SEC1_1-Pad6)") (class "Default")
      (node (ref "T2") (pin "6") (pinfunction "SEC1_1_6") (pintype "bidirectional"))
    )
    (net (code "72") (name "unconnected-(T2-SEC1_2-Pad7)") (class "Default")
      (node (ref "T2") (pin "7") (pinfunction "SEC1_2_7") (pintype "bidirectional"))
    )
    (net (code "73") (name "unconnected-(T3-SEC1_1-Pad6)") (class "Default")
      (node (ref "T3") (pin "6") (pinfunction "SEC1_1_6") (pintype "bidirectional"))
    )
    (net (code "74") (name "unconnected-(T3-SEC1_2-Pad7)") (class "Default")
      (node (ref "T3") (pin "7") (pinfunction "SEC1_2_7") (pintype "bidirectional"))
    )
    (net (code "75") (name "unconnected-(T4-SEC1_1-Pad6)") (class "Default")
      (node (ref "T4") (pin "6") (pinfunction "SEC1_1_6") (pintype "bidirectional"))
    )
    (net (code "76") (name "unconnected-(T4-SEC1_2-Pad7)") (class "Default")
      (node (ref "T4") (pin "7") (pinfunction "SEC1_2_7") (pintype "bidirectional"))
    )
  )
)
